# Controller_final.net
KiCad netlist of a schematic drawn in Altium Designer
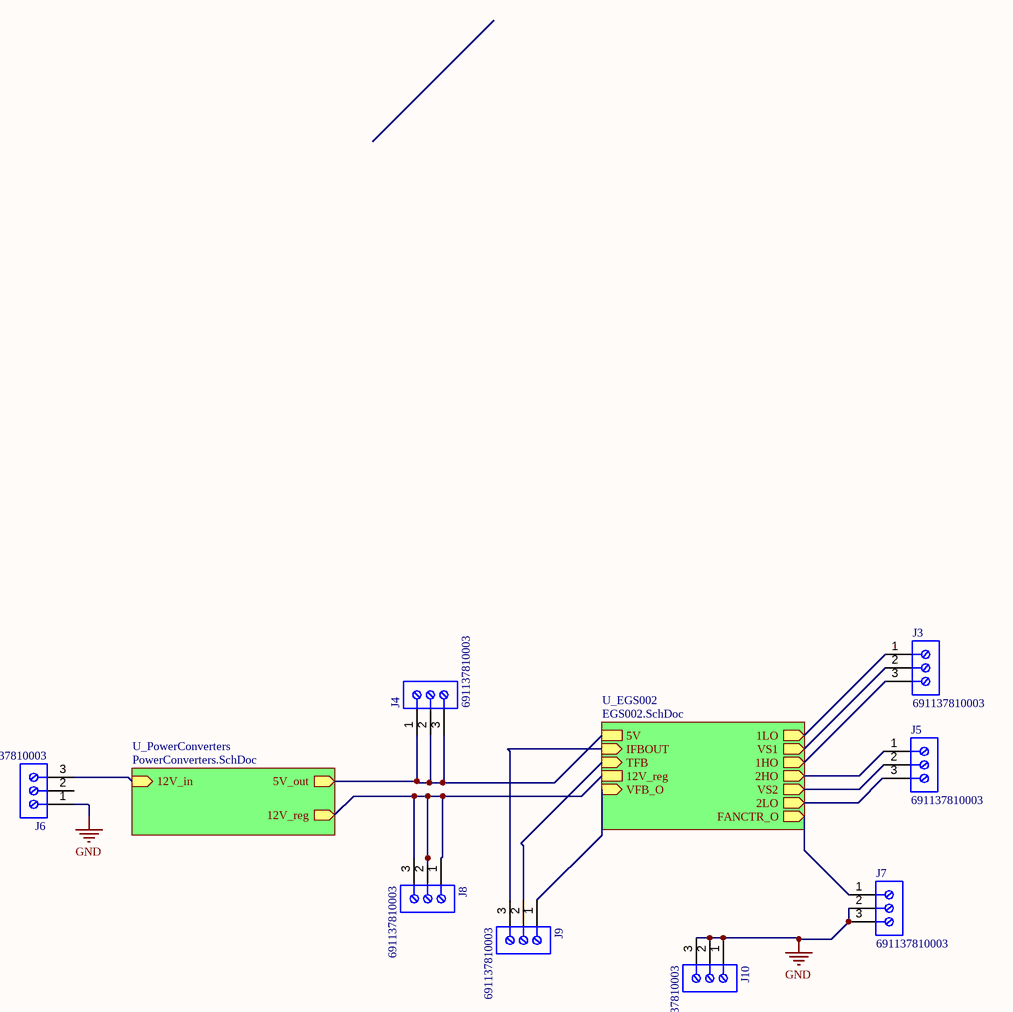
[diagram p0: Controller_final.SchDoc]

(export (version "E")
  (design (tool "Eeschema 10.0.6"))
  (components
    (comp (ref "J3")
      (value "691137810003")
      (footprint "691137810003")
      (description "10.00 mm Terminal Block, Horizontal Entr")
      (libsource (lib "Altium Content Vault") (part "TBL - 1R - 03P - Screw"))
    )
    (comp (ref "J4")
      (value "691137810003")
      (footprint "691137810003")
      (description "10.00 mm Terminal Block, Horizontal Entr")
      (libsource (lib "Altium Content Vault") (part "TBL - 1R - 03P - Screw"))
    )
    (comp (ref "J5")
      (value "691137810003")
      (footprint "691137810003")
      (description "10.00 mm Terminal Block, Horizontal Entr")
      (libsource (lib "Altium Content Vault") (part "TBL - 1R - 03P - Screw"))
    )
    (comp (ref "J6")
      (value "691137810003")
      (footprint "691137810003")
      (description "10.00 mm Terminal Block, Horizontal Entr")
      (libsource (lib "Altium Content Vault") (part "TBL - 1R - 03P - Screw"))
    )
    (comp (ref "J7")
      (value "691137810003")
      (footprint "691137810003")
      (description "10.00 mm Terminal Block, Horizontal Entr")
      (libsource (lib "Altium Content Vault") (part "TBL - 1R - 03P - Screw"))
    )
    (comp (ref "J8")
      (value "691137810003")
      (footprint "691137810003")
      (description "10.00 mm Terminal Block, Horizontal Entr")
      (libsource (lib "Altium Content Vault") (part "TBL - 1R - 03P - Screw"))
    )
    (comp (ref "J9")
      (value "691137810003")
      (footprint "691137810003")
      (description "10.00 mm Terminal Block, Horizontal Entr")
      (libsource (lib "Altium Content Vault") (part "TBL - 1R - 03P - Screw"))
    )
    (comp (ref "J10")
      (value "691137810003")
      (footprint "691137810003")
      (description "10.00 mm Terminal Block, Horizontal Entr")
      (libsource (lib "Altium Content Vault") (part "TBL - 1R - 03P - Screw"))
    )
  )
  (nets
    (net (code "1") (name "/1HO") (class "Default")
      (node (ref "J3") (pin "3") (pinfunction "3_3") (pintype "passive"))
    )
    (net (code "2") (name "/1LO") (class "Default")
      (node (ref "J3") (pin "1") (pinfunction "1_1") (pintype "passive"))
    )
    (net (code "3") (name "/2HO") (class "Default")
      (node (ref "J5") (pin "1") (pinfunction "1_1") (pintype "passive"))
    )
    (net (code "4") (name "/2LO") (class "Default")
      (node (ref "J5") (pin "3") (pinfunction "3_3") (pintype "passive"))
    )
    (net (code "5") (name "/5V_out") (class "Default")
      (node (ref "J4") (pin "1") (pinfunction "1_1") (pintype "passive"))
      (node (ref "J4") (pin "2") (pinfunction "2_2") (pintype "passive"))
      (node (ref "J4") (pin "3") (pinfunction "3_3") (pintype "passive"))
    )
    (net (code "6") (name "/12V_in") (class "Default")
      (node (ref "J6") (pin "3") (pinfunction "3_3") (pintype "passive"))
    )
    (net (code "7") (name "/12V_reg") (class "Default")
      (node (ref "J8") (pin "1") (pinfunction "1_1") (pintype "passive"))
      (node (ref "J8") (pin "2") (pinfunction "2_2") (pintype "passive"))
      (node (ref "J8") (pin "3") (pinfunction "3_3") (pintype "passive"))
    )
    (net (code "8") (name "/FANCTR_O") (class "Default")
      (node (ref "J7") (pin "1") (pinfunction "1_1") (pintype "passive"))
    )
    (net (code "9") (name "/IFBOUT") (class "Default")
      (node (ref "J9") (pin "3") (pinfunction "3_3") (pintype "passive"))
    )
    (net (code "10") (name "/TFB") (class "Default")
      (node (ref "J9") (pin "2") (pinfunction "2_2") (pintype "passive"))
    )
    (net (code "11") (name "/VFB_O") (class "Default")
      (node (ref "J9") (pin "1") (pinfunction "1_1") (pintype "passive"))
    )
    (net (code "12") (name "/VS1") (class "Default")
      (node (ref "J3") (pin "2") (pinfunction "2_2") (pintype "passive"))
    )
    (net (code "13") (name "/VS2") (class "Default")
      (node (ref "J5") (pin "2") (pinfunction "2_2") (pintype "passive"))
    )
    (net (code "14") (name "GND") (class "Default")
      (node (ref "J10") (pin "1") (pinfunction "1_1") (pintype "passive"))
      (node (ref "J10") (pin "2") (pinfunction "2_2") (pintype "passive"))
      (node (ref "J10") (pin "3") (pinfunction "3_3") (pintype "passive"))
      (node (ref "J6") (pin "1") (pinfunction "1_1") (pintype "passive"))
      (node (ref "J7") (pin "2") (pinfunction "2_2") (pintype "passive"))
      (node (ref "J7") (pin "3") (pinfunction "3_3") (pintype "passive"))
    )
    (net (code "15") (name "unconnected-(J6-Pad2)") (class "Default")
      (node (ref "J6") (pin "2") (pinfunction "2_2") (pintype "passive"))
    )
  )
)
